# 3bp.net
KiCad netlist of a schematic drawn in EAGLE
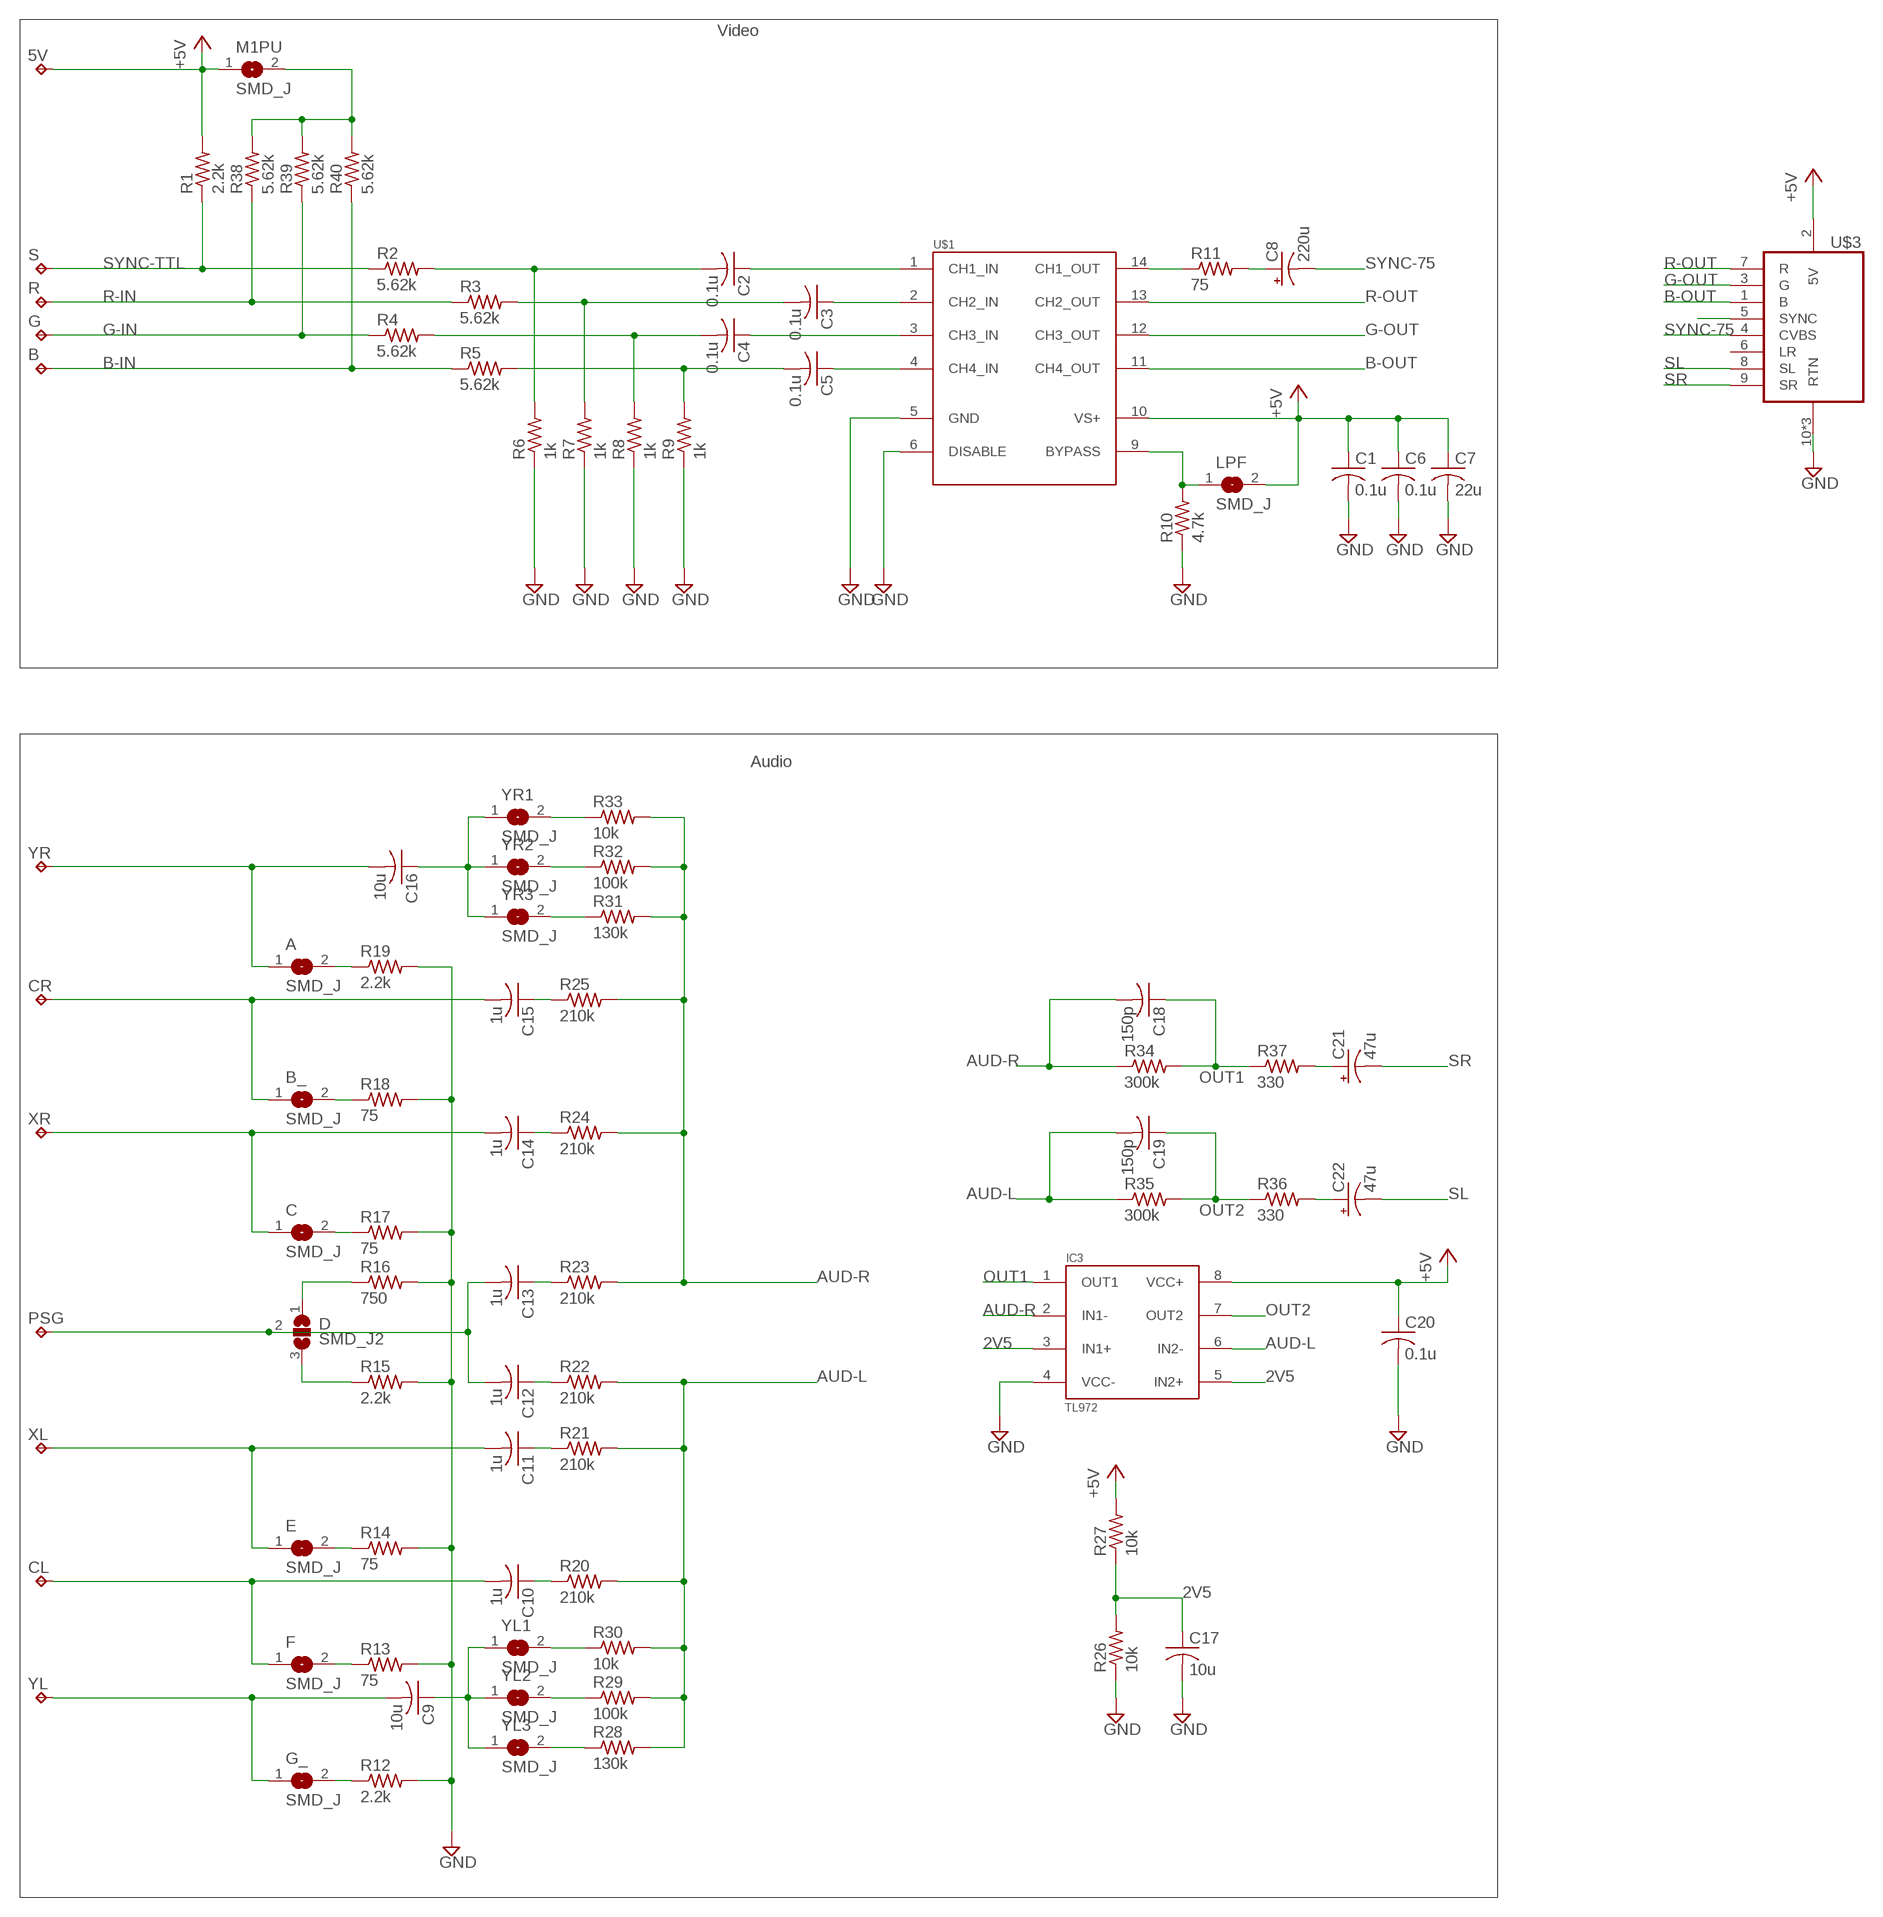
[diagram p0: schematic, sheet 1]

(export (version "E")
  (design (tool "Eeschema 10.0.6"))
  (components
    (comp (ref "5V")
      (value "PAD_50X80")
      (footprint "eagle-import:TP_50X80")
      (libsource (lib "eagle-import") (part "PAD_50X80"))
    )
    (comp (ref "A")
      (value "SMD_J")
      (footprint "eagle-import:SJ")
      (libsource (lib "eagle-import") (part "SMD_J"))
    )
    (comp (ref "B")
      (value "PAD_50X80")
      (footprint "eagle-import:TP_50X80")
      (libsource (lib "eagle-import") (part "PAD_50X80"))
    )
    (comp (ref "B_")
      (value "SMD_J")
      (footprint "eagle-import:SJ")
      (libsource (lib "eagle-import") (part "SMD_J"))
    )
    (comp (ref "C")
      (value "SMD_J")
      (footprint "eagle-import:SJ")
      (libsource (lib "eagle-import") (part "SMD_J"))
    )
    (comp (ref "C1")
      (value "0.1u")
      (footprint "eagle-import:C0603")
      (libsource (lib "eagle-import") (part "C-USC0603"))
    )
    (comp (ref "C2")
      (value "0.1u")
      (footprint "eagle-import:C0603")
      (libsource (lib "eagle-import") (part "C-USC0603"))
    )
    (comp (ref "C3")
      (value "0.1u")
      (footprint "eagle-import:C0603")
      (libsource (lib "eagle-import") (part "C-USC0603"))
    )
    (comp (ref "C4")
      (value "0.1u")
      (footprint "eagle-import:C0603")
      (libsource (lib "eagle-import") (part "C-USC0603"))
    )
    (comp (ref "C5")
      (value "0.1u")
      (footprint "eagle-import:C0603")
      (libsource (lib "eagle-import") (part "C-USC0603"))
    )
    (comp (ref "C6")
      (value "0.1u")
      (footprint "eagle-import:C0603")
      (libsource (lib "eagle-import") (part "C-USC0603"))
    )
    (comp (ref "C7")
      (value "22u")
      (footprint "eagle-import:C1206")
      (libsource (lib "eagle-import") (part "C-USC1206"))
    )
    (comp (ref "C8")
      (value "220u")
      (footprint "eagle-import:CT3528")
      (libsource (lib "eagle-import") (part "CPOL-USCT3528"))
    )
    (comp (ref "C9")
      (value "10u")
      (footprint "eagle-import:C0805")
      (libsource (lib "eagle-import") (part "C-USC0805"))
    )
    (comp (ref "C10")
      (value "1u")
      (footprint "eagle-import:C0603")
      (libsource (lib "eagle-import") (part "C-USC0603"))
    )
    (comp (ref "C11")
      (value "1u")
      (footprint "eagle-import:C0603")
      (libsource (lib "eagle-import") (part "C-USC0603"))
    )
    (comp (ref "C12")
      (value "1u")
      (footprint "eagle-import:C0603")
      (libsource (lib "eagle-import") (part "C-USC0603"))
    )
    (comp (ref "C13")
      (value "1u")
      (footprint "eagle-import:C0603")
      (libsource (lib "eagle-import") (part "C-USC0603"))
    )
    (comp (ref "C14")
      (value "1u")
      (footprint "eagle-import:C0603")
      (libsource (lib "eagle-import") (part "C-USC0603"))
    )
    (comp (ref "C15")
      (value "1u")
      (footprint "eagle-import:C0603")
      (libsource (lib "eagle-import") (part "C-USC0603"))
    )
    (comp (ref "C16")
      (value "10u")
      (footprint "eagle-import:C0805")
      (libsource (lib "eagle-import") (part "C-USC0805"))
    )
    (comp (ref "C17")
      (value "10u")
      (footprint "eagle-import:C1206")
      (libsource (lib "eagle-import") (part "C-USC1206"))
    )
    (comp (ref "C18")
      (value "150p")
      (footprint "eagle-import:C0603")
      (libsource (lib "eagle-import") (part "C-USC0603"))
    )
    (comp (ref "C19")
      (value "150p")
      (footprint "eagle-import:C0603")
      (libsource (lib "eagle-import") (part "C-USC0603"))
    )
    (comp (ref "C20")
      (value "0.1u")
      (footprint "eagle-import:C0603")
      (libsource (lib "eagle-import") (part "C-USC0603"))
    )
    (comp (ref "C21")
      (value "47u")
      (footprint "eagle-import:CT3528")
      (libsource (lib "eagle-import") (part "CPOL-USCT3528"))
    )
    (comp (ref "C22")
      (value "47u")
      (footprint "eagle-import:CT3528")
      (libsource (lib "eagle-import") (part "CPOL-USCT3528"))
    )
    (comp (ref "CL")
      (value "PAD_50X80")
      (footprint "eagle-import:TP_50X80")
      (libsource (lib "eagle-import") (part "PAD_50X80"))
    )
    (comp (ref "CR")
      (value "PAD_50X80")
      (footprint "eagle-import:TP_50X80")
      (libsource (lib "eagle-import") (part "PAD_50X80"))
    )
    (comp (ref "D")
      (value "SMD_J2")
      (footprint "eagle-import:SJ_2")
      (libsource (lib "eagle-import") (part "SMD_J2"))
    )
    (comp (ref "E")
      (value "SMD_J")
      (footprint "eagle-import:SJ")
      (libsource (lib "eagle-import") (part "SMD_J"))
    )
    (comp (ref "F")
      (value "SMD_J")
      (footprint "eagle-import:SJ")
      (libsource (lib "eagle-import") (part "SMD_J"))
    )
    (comp (ref "G")
      (value "PAD_50X80")
      (footprint "eagle-import:TP_50X80")
      (libsource (lib "eagle-import") (part "PAD_50X80"))
    )
    (comp (ref "G_")
      (value "SMD_J")
      (footprint "eagle-import:SJ")
      (libsource (lib "eagle-import") (part "SMD_J"))
    )
    (comp (ref "IC3")
      (value "TL972")
      (footprint "eagle-import:SOIC8")
      (libsource (lib "eagle-import") (part "TL972"))
    )
    (comp (ref "LPF")
      (value "SMD_J")
      (footprint "eagle-import:SJ")
      (libsource (lib "eagle-import") (part "SMD_J"))
    )
    (comp (ref "M1PU")
      (value "SMD_J")
      (footprint "eagle-import:SJ")
      (libsource (lib "eagle-import") (part "SMD_J"))
    )
    (comp (ref "PSG")
      (value "PAD_50X80")
      (footprint "eagle-import:TP_50X80")
      (libsource (lib "eagle-import") (part "PAD_50X80"))
    )
    (comp (ref "R")
      (value "PAD_50X80")
      (footprint "eagle-import:TP_50X80")
      (libsource (lib "eagle-import") (part "PAD_50X80"))
    )
    (comp (ref "R1")
      (value "2.2k")
      (footprint "eagle-import:R0603")
      (libsource (lib "eagle-import") (part "R-US_R0603"))
    )
    (comp (ref "R2")
      (value "5.62k")
      (footprint "eagle-import:R0603")
      (libsource (lib "eagle-import") (part "R-US_R0603"))
    )
    (comp (ref "R3")
      (value "5.62k")
      (footprint "eagle-import:R0603")
      (libsource (lib "eagle-import") (part "R-US_R0603"))
    )
    (comp (ref "R4")
      (value "5.62k")
      (footprint "eagle-import:R0603")
      (libsource (lib "eagle-import") (part "R-US_R0603"))
    )
    (comp (ref "R5")
      (value "5.62k")
      (footprint "eagle-import:R0603")
      (libsource (lib "eagle-import") (part "R-US_R0603"))
    )
    (comp (ref "R6")
      (value "1k")
      (footprint "eagle-import:R0603")
      (libsource (lib "eagle-import") (part "R-US_R0603"))
    )
    (comp (ref "R7")
      (value "1k")
      (footprint "eagle-import:R0603")
      (libsource (lib "eagle-import") (part "R-US_R0603"))
    )
    (comp (ref "R8")
      (value "1k")
      (footprint "eagle-import:R0603")
      (libsource (lib "eagle-import") (part "R-US_R0603"))
    )
    (comp (ref "R9")
      (value "1k")
      (footprint "eagle-import:R0603")
      (libsource (lib "eagle-import") (part "R-US_R0603"))
    )
    (comp (ref "R10")
      (value "4.7k")
      (footprint "eagle-import:R0603")
      (libsource (lib "eagle-import") (part "R-US_R0603"))
    )
    (comp (ref "R11")
      (value "75")
      (footprint "eagle-import:R0603")
      (libsource (lib "eagle-import") (part "R-US_R0603"))
    )
    (comp (ref "R12")
      (value "2.2k")
      (footprint "eagle-import:R0603")
      (libsource (lib "eagle-import") (part "R-US_R0603"))
    )
    (comp (ref "R13")
      (value "75")
      (footprint "eagle-import:R0603")
      (libsource (lib "eagle-import") (part "R-US_R0603"))
    )
    (comp (ref "R14")
      (value "75")
      (footprint "eagle-import:R0603")
      (libsource (lib "eagle-import") (part "R-US_R0603"))
    )
    (comp (ref "R15")
      (value "2.2k")
      (footprint "eagle-import:R0603")
      (libsource (lib "eagle-import") (part "R-US_R0603"))
    )
    (comp (ref "R16")
      (value "750")
      (footprint "eagle-import:R0603")
      (libsource (lib "eagle-import") (part "R-US_R0603"))
    )
    (comp (ref "R17")
      (value "75")
      (footprint "eagle-import:R0603")
      (libsource (lib "eagle-import") (part "R-US_R0603"))
    )
    (comp (ref "R18")
      (value "75")
      (footprint "eagle-import:R0603")
      (libsource (lib "eagle-import") (part "R-US_R0603"))
    )
    (comp (ref "R19")
      (value "2.2k")
      (footprint "eagle-import:R0603")
      (libsource (lib "eagle-import") (part "R-US_R0603"))
    )
    (comp (ref "R20")
      (value "210k")
      (footprint "eagle-import:R0603")
      (libsource (lib "eagle-import") (part "R-US_R0603"))
    )
    (comp (ref "R21")
      (value "210k")
      (footprint "eagle-import:R0603")
      (libsource (lib "eagle-import") (part "R-US_R0603"))
    )
    (comp (ref "R22")
      (value "210k")
      (footprint "eagle-import:R0603")
      (libsource (lib "eagle-import") (part "R-US_R0603"))
    )
    (comp (ref "R23")
      (value "210k")
      (footprint "eagle-import:R0603")
      (libsource (lib "eagle-import") (part "R-US_R0603"))
    )
    (comp (ref "R24")
      (value "210k")
      (footprint "eagle-import:R0603")
      (libsource (lib "eagle-import") (part "R-US_R0603"))
    )
    (comp (ref "R25")
      (value "210k")
      (footprint "eagle-import:R0603")
      (libsource (lib "eagle-import") (part "R-US_R0603"))
    )
    (comp (ref "R26")
      (value "10k")
      (footprint "eagle-import:R0603")
      (libsource (lib "eagle-import") (part "R-US_R0603"))
    )
    (comp (ref "R27")
      (value "10k")
      (footprint "eagle-import:R0603")
      (libsource (lib "eagle-import") (part "R-US_R0603"))
    )
    (comp (ref "R28")
      (value "130k")
      (footprint "eagle-import:R0603")
      (libsource (lib "eagle-import") (part "R-US_R0603"))
    )
    (comp (ref "R29")
      (value "100k")
      (footprint "eagle-import:R0603")
      (libsource (lib "eagle-import") (part "R-US_R0603"))
    )
    (comp (ref "R30")
      (value "10k")
      (footprint "eagle-import:R0603")
      (libsource (lib "eagle-import") (part "R-US_R0603"))
    )
    (comp (ref "R31")
      (value "130k")
      (footprint "eagle-import:R0603")
      (libsource (lib "eagle-import") (part "R-US_R0603"))
    )
    (comp (ref "R32")
      (value "100k")
      (footprint "eagle-import:R0603")
      (libsource (lib "eagle-import") (part "R-US_R0603"))
    )
    (comp (ref "R33")
      (value "10k")
      (footprint "eagle-import:R0603")
      (libsource (lib "eagle-import") (part "R-US_R0603"))
    )
    (comp (ref "R34")
      (value "300k")
      (footprint "eagle-import:R0603")
      (libsource (lib "eagle-import") (part "R-US_R0603"))
    )
    (comp (ref "R35")
      (value "300k")
      (footprint "eagle-import:R0603")
      (libsource (lib "eagle-import") (part "R-US_R0603"))
    )
    (comp (ref "R36")
      (value "330")
      (footprint "eagle-import:R0603")
      (libsource (lib "eagle-import") (part "R-US_R0603"))
    )
    (comp (ref "R37")
      (value "330")
      (footprint "eagle-import:R0603")
      (libsource (lib "eagle-import") (part "R-US_R0603"))
    )
    (comp (ref "R38")
      (value "5.62k")
      (footprint "eagle-import:R0603")
      (libsource (lib "eagle-import") (part "R-US_R0603"))
    )
    (comp (ref "R39")
      (value "5.62k")
      (footprint "eagle-import:R0603")
      (libsource (lib "eagle-import") (part "R-US_R0603"))
    )
    (comp (ref "R40")
      (value "5.62k")
      (footprint "eagle-import:R0603")
      (libsource (lib "eagle-import") (part "R-US_R0603"))
    )
    (comp (ref "S")
      (value "PAD_50X80")
      (footprint "eagle-import:TP_50X80")
      (libsource (lib "eagle-import") (part "PAD_50X80"))
    )
    (comp (ref "U$1")
      (value "THS7374IPWR")
      (footprint "eagle-import:TSSOP14")
      (libsource (lib "eagle-import") (part "THS7374IPWR"))
    )
    (comp (ref "U$3")
      (value "MD-90SM")
      (footprint "eagle-import:MD90SM")
      (libsource (lib "eagle-import") (part "MD-90SM"))
    )
    (comp (ref "XL")
      (value "PAD_50X80")
      (footprint "eagle-import:TP_50X80")
      (libsource (lib "eagle-import") (part "PAD_50X80"))
    )
    (comp (ref "XR")
      (value "PAD_50X80")
      (footprint "eagle-import:TP_50X80")
      (libsource (lib "eagle-import") (part "PAD_50X80"))
    )
    (comp (ref "YL")
      (value "PAD_50X80")
      (footprint "eagle-import:TP_50X80")
      (libsource (lib "eagle-import") (part "PAD_50X80"))
    )
    (comp (ref "YL1")
      (value "SMD_J")
      (footprint "eagle-import:SJ")
      (libsource (lib "eagle-import") (part "SMD_J"))
    )
    (comp (ref "YL2")
      (value "SMD_J")
      (footprint "eagle-import:SJ")
      (libsource (lib "eagle-import") (part "SMD_J"))
    )
    (comp (ref "YL3")
      (value "SMD_J")
      (footprint "eagle-import:SJ")
      (libsource (lib "eagle-import") (part "SMD_J"))
    )
    (comp (ref "YR")
      (value "PAD_50X80")
      (footprint "eagle-import:TP_50X80")
      (libsource (lib "eagle-import") (part "PAD_50X80"))
    )
    (comp (ref "YR1")
      (value "SMD_J")
      (footprint "eagle-import:SJ")
      (libsource (lib "eagle-import") (part "SMD_J"))
    )
    (comp (ref "YR2")
      (value "SMD_J")
      (footprint "eagle-import:SJ")
      (libsource (lib "eagle-import") (part "SMD_J"))
    )
    (comp (ref "YR3")
      (value "SMD_J")
      (footprint "eagle-import:SJ")
      (libsource (lib "eagle-import") (part "SMD_J"))
    )
  )
  (nets
    (net (code "1") (name "+5V") (class "Default")
      (node (ref "5V") (pin "TP") (pinfunction "TP_TP") (pintype "input"))
      (node (ref "C1") (pin "1") (pinfunction "1_1") (pintype "passive"))
      (node (ref "C20") (pin "1") (pinfunction "1_1") (pintype "passive"))
      (node (ref "C6") (pin "1") (pinfunction "1_1") (pintype "passive"))
      (node (ref "C7") (pin "1") (pinfunction "1_1") (pintype "passive"))
      (node (ref "IC3") (pin "8") (pinfunction "VCC+_8") (pintype "bidirectional"))
      (node (ref "LPF") (pin "2") (pinfunction "2_2") (pintype "passive"))
      (node (ref "M1PU") (pin "1") (pinfunction "1_1") (pintype "passive"))
      (node (ref "R1") (pin "2") (pinfunction "2_2") (pintype "passive"))
      (node (ref "R27") (pin "2") (pinfunction "2_2") (pintype "passive"))
      (node (ref "U$1") (pin "10") (pinfunction "VS+_10") (pintype "bidirectional"))
      (node (ref "U$3") (pin "2") (pinfunction "5V_2") (pintype "bidirectional"))
    )
    (net (code "2") (name "/2V5") (class "Default")
      (node (ref "C17") (pin "1") (pinfunction "1_1") (pintype "passive"))
      (node (ref "IC3") (pin "3") (pinfunction "IN1+_3") (pintype "bidirectional"))
      (node (ref "IC3") (pin "5") (pinfunction "IN2+_5") (pintype "bidirectional"))
      (node (ref "R26") (pin "2") (pinfunction "2_2") (pintype "passive"))
      (node (ref "R27") (pin "1") (pinfunction "1_1") (pintype "passive"))
    )
    (net (code "3") (name "/AUD-L") (class "Default")
      (node (ref "C19") (pin "2") (pinfunction "2_2") (pintype "passive"))
      (node (ref "IC3") (pin "6") (pinfunction "IN2-_6") (pintype "bidirectional"))
      (node (ref "R20") (pin "2") (pinfunction "2_2") (pintype "passive"))
      (node (ref "R21") (pin "2") (pinfunction "2_2") (pintype "passive"))
      (node (ref "R22") (pin "2") (pinfunction "2_2") (pintype "passive"))
      (node (ref "R28") (pin "2") (pinfunction "2_2") (pintype "passive"))
      (node (ref "R29") (pin "2") (pinfunction "2_2") (pintype "passive"))
      (node (ref "R30") (pin "2") (pinfunction "2_2") (pintype "passive"))
      (node (ref "R35") (pin "1") (pinfunction "1_1") (pintype "passive"))
    )
    (net (code "4") (name "/AUD-R") (class "Default")
      (node (ref "C18") (pin "2") (pinfunction "2_2") (pintype "passive"))
      (node (ref "IC3") (pin "2") (pinfunction "IN1-_2") (pintype "bidirectional"))
      (node (ref "R23") (pin "2") (pinfunction "2_2") (pintype "passive"))
      (node (ref "R24") (pin "2") (pinfunction "2_2") (pintype "passive"))
      (node (ref "R25") (pin "2") (pinfunction "2_2") (pintype "passive"))
      (node (ref "R31") (pin "2") (pinfunction "2_2") (pintype "passive"))
      (node (ref "R32") (pin "2") (pinfunction "2_2") (pintype "passive"))
      (node (ref "R33") (pin "2") (pinfunction "2_2") (pintype "passive"))
      (node (ref "R34") (pin "1") (pinfunction "1_1") (pintype "passive"))
    )
    (net (code "5") (name "/B-IN") (class "Default")
      (node (ref "B") (pin "TP") (pinfunction "TP_TP") (pintype "input"))
      (node (ref "R40") (pin "1") (pinfunction "1_1") (pintype "passive"))
      (node (ref "R5") (pin "1") (pinfunction "1_1") (pintype "passive"))
    )
    (net (code "6") (name "/B-OUT") (class "Default")
      (node (ref "U$1") (pin "11") (pinfunction "CH4_OUT_11") (pintype "bidirectional"))
      (node (ref "U$3") (pin "1") (pinfunction "B_1") (pintype "bidirectional"))
    )
    (net (code "7") (name "/G-IN") (class "Default")
      (node (ref "G") (pin "TP") (pinfunction "TP_TP") (pintype "input"))
      (node (ref "R39") (pin "1") (pinfunction "1_1") (pintype "passive"))
      (node (ref "R4") (pin "1") (pinfunction "1_1") (pintype "passive"))
    )
    (net (code "8") (name "/G-OUT") (class "Default")
      (node (ref "U$1") (pin "12") (pinfunction "CH3_OUT_12") (pintype "bidirectional"))
      (node (ref "U$3") (pin "3") (pinfunction "G_3") (pintype "bidirectional"))
    )
    (net (code "9") (name "/OUT1") (class "Default")
      (node (ref "C18") (pin "1") (pinfunction "1_1") (pintype "passive"))
      (node (ref "IC3") (pin "1") (pinfunction "OUT1_1") (pintype "bidirectional"))
      (node (ref "R34") (pin "2") (pinfunction "2_2") (pintype "passive"))
      (node (ref "R37") (pin "1") (pinfunction "1_1") (pintype "passive"))
    )
    (net (code "10") (name "/OUT2") (class "Default")
      (node (ref "C19") (pin "1") (pinfunction "1_1") (pintype "passive"))
      (node (ref "IC3") (pin "7") (pinfunction "OUT2_7") (pintype "bidirectional"))
      (node (ref "R35") (pin "2") (pinfunction "2_2") (pintype "passive"))
      (node (ref "R36") (pin "1") (pinfunction "1_1") (pintype "passive"))
    )
    (net (code "11") (name "/R-IN") (class "Default")
      (node (ref "R") (pin "TP") (pinfunction "TP_TP") (pintype "input"))
      (node (ref "R3") (pin "1") (pinfunction "1_1") (pintype "passive"))
      (node (ref "R38") (pin "1") (pinfunction "1_1") (pintype "passive"))
    )
    (net (code "12") (name "/R-OUT") (class "Default")
      (node (ref "U$1") (pin "13") (pinfunction "CH2_OUT_13") (pintype "bidirectional"))
      (node (ref "U$3") (pin "7") (pinfunction "R_7") (pintype "bidirectional"))
    )
    (net (code "13") (name "/SL") (class "Default")
      (node (ref "C22") (pin "-") (pinfunction "-_-") (pintype "passive"))
      (node (ref "U$3") (pin "8") (pinfunction "SL_8") (pintype "bidirectional"))
    )
    (net (code "14") (name "/SR") (class "Default")
      (node (ref "C21") (pin "-") (pinfunction "-_-") (pintype "passive"))
      (node (ref "U$3") (pin "9") (pinfunction "SR_9") (pintype "bidirectional"))
    )
    (net (code "15") (name "/SYNC-75") (class "Default")
      (node (ref "C8") (pin "-") (pinfunction "-_-") (pintype "passive"))
      (node (ref "U$3") (pin "4") (pinfunction "CVBS_4") (pintype "bidirectional"))
    )
    (net (code "16") (name "/SYNC-TTL") (class "Default")
      (node (ref "R1") (pin "1") (pinfunction "1_1") (pintype "passive"))
      (node (ref "R2") (pin "1") (pinfunction "1_1") (pintype "passive"))
      (node (ref "S") (pin "TP") (pinfunction "TP_TP") (pintype "input"))
    )
    (net (code "17") (name "GND") (class "Default")
      (node (ref "C1") (pin "2") (pinfunction "2_2") (pintype "passive"))
      (node (ref "C17") (pin "2") (pinfunction "2_2") (pintype "passive"))
      (node (ref "C20") (pin "2") (pinfunction "2_2") (pintype "passive"))
      (node (ref "C6") (pin "2") (pinfunction "2_2") (pintype "passive"))
      (node (ref "C7") (pin "2") (pinfunction "2_2") (pintype "passive"))
      (node (ref "IC3") (pin "4") (pinfunction "VCC-_4") (pintype "bidirectional"))
      (node (ref "R10") (pin "1") (pinfunction "1_1") (pintype "passive"))
      (node (ref "R12") (pin "2") (pinfunction "2_2") (pintype "passive"))
      (node (ref "R13") (pin "2") (pinfunction "2_2") (pintype "passive"))
      (node (ref "R14") (pin "2") (pinfunction "2_2") (pintype "passive"))
      (node (ref "R15") (pin "2") (pinfunction "2_2") (pintype "passive"))
      (node (ref "R16") (pin "2") (pinfunction "2_2") (pintype "passive"))
      (node (ref "R17") (pin "2") (pinfunction "2_2") (pintype "passive"))
      (node (ref "R18") (pin "2") (pinfunction "2_2") (pintype "passive"))
      (node (ref "R19") (pin "2") (pinfunction "2_2") (pintype "passive"))
      (node (ref "R26") (pin "1") (pinfunction "1_1") (pintype "passive"))
      (node (ref "R6") (pin "1") (pinfunction "1_1") (pintype "passive"))
      (node (ref "R7") (pin "1") (pinfunction "1_1") (pintype "passive"))
      (node (ref "R8") (pin "1") (pinfunction "1_1") (pintype "passive"))
      (node (ref "R9") (pin "1") (pinfunction "1_1") (pintype "passive"))
      (node (ref "U$1") (pin "5") (pinfunction "GND_5") (pintype "bidirectional"))
      (node (ref "U$1") (pin "6") (pinfunction "DISABLE_6") (pintype "bidirectional"))
      (node (ref "U$3") (pin "10") (pinfunction "RTN_10") (pintype "bidirectional"))
      (node (ref "U$3") (pin "11") (pinfunction "RTN_11") (pintype "bidirectional"))
      (node (ref "U$3") (pin "12") (pinfunction "RTN_12") (pintype "bidirectional"))
    )
    (net (code "18") (name "Net-(A-Pad1)") (class "Default")
      (node (ref "A") (pin "1") (pinfunction "1_1") (pintype "passive"))
      (node (ref "C16") (pin "2") (pinfunction "2_2") (pintype "passive"))
      (node (ref "YR") (pin "TP") (pinfunction "TP_TP") (pintype "input"))
    )
    (net (code "19") (name "Net-(A-Pad2)") (class "Default")
      (node (ref "A") (pin "2") (pinfunction "2_2") (pintype "passive"))
      (node (ref "R19") (pin "1") (pinfunction "1_1") (pintype "passive"))
    )
    (net (code "20") (name "Net-(B_-Pad1)") (class "Default")
      (node (ref "B_") (pin "1") (pinfunction "1_1") (pintype "passive"))
      (node (ref "C15") (pin "2") (pinfunction "2_2") (pintype "passive"))
      (node (ref "CR") (pin "TP") (pinfunction "TP_TP") (pintype "input"))
    )
    (net (code "21") (name "Net-(B_-Pad2)") (class "Default")
      (node (ref "B_") (pin "2") (pinfunction "2_2") (pintype "passive"))
      (node (ref "R18") (pin "1") (pinfunction "1_1") (pintype "passive"))
    )
    (net (code "22") (name "Net-(C-Pad1)") (class "Default")
      (node (ref "C") (pin "1") (pinfunction "1_1") (pintype "passive"))
      (node (ref "C14") (pin "2") (pinfunction "2_2") (pintype "passive"))
      (node (ref "XR") (pin "TP") (pinfunction "TP_TP") (pintype "input"))
    )
    (net (code "23") (name "Net-(C-Pad2)") (class "Default")
      (node (ref "C") (pin "2") (pinfunction "2_2") (pintype "passive"))
      (node (ref "R17") (pin "1") (pinfunction "1_1") (pintype "passive"))
    )
    (net (code "24") (name "Net-(C2-Pad2)") (class "Default")
      (node (ref "C2") (pin "2") (pinfunction "2_2") (pintype "passive"))
      (node (ref "R2") (pin "2") (pinfunction "2_2") (pintype "passive"))
      (node (ref "R6") (pin "2") (pinfunction "2_2") (pintype "passive"))
    )
    (net (code "25") (name "Net-(C3-Pad2)") (class "Default")
      (node (ref "C3") (pin "2") (pinfunction "2_2") (pintype "passive"))
      (node (ref "R3") (pin "2") (pinfunction "2_2") (pintype "passive"))
      (node (ref "R7") (pin "2") (pinfunction "2_2") (pintype "passive"))
    )
    (net (code "26") (name "Net-(C4-Pad2)") (class "Default")
      (node (ref "C4") (pin "2") (pinfunction "2_2") (pintype "passive"))
      (node (ref "R4") (pin "2") (pinfunction "2_2") (pintype "passive"))
      (node (ref "R8") (pin "2") (pinfunction "2_2") (pintype "passive"))
    )
    (net (code "27") (name "Net-(C5-Pad2)") (class "Default")
      (node (ref "C5") (pin "2") (pinfunction "2_2") (pintype "passive"))
      (node (ref "R5") (pin "2") (pinfunction "2_2") (pintype "passive"))
      (node (ref "R9") (pin "2") (pinfunction "2_2") (pintype "passive"))
    )
    (net (code "28") (name "Net-(C8-Pad+)") (class "Default")
      (node (ref "C8") (pin "+") (pinfunction "+_+") (pintype "passive"))
      (node (ref "R11") (pin "2") (pinfunction "2_2") (pintype "passive"))
    )
    (net (code "29") (name "Net-(C9-Pad1)") (class "Default")
      (node (ref "C9") (pin "1") (pinfunction "1_1") (pintype "passive"))
      (node (ref "YL1") (pin "1") (pinfunction "1_1") (pintype "passive"))
      (node (ref "YL2") (pin "1") (pinfunction "1_1") (pintype "passive"))
      (node (ref "YL3") (pin "1") (pinfunction "1_1") (pintype "passive"))
    )
    (net (code "30") (name "Net-(C9-Pad2)") (class "Default")
      (node (ref "C9") (pin "2") (pinfunction "2_2") (pintype "passive"))
      (node (ref "G_") (pin "1") (pinfunction "1_1") (pintype "passive"))
      (node (ref "YL") (pin "TP") (pinfunction "TP_TP") (pintype "input"))
    )
    (net (code "31") (name "Net-(C10-Pad1)") (class "Default")
      (node (ref "C10") (pin "1") (pinfunction "1_1") (pintype "passive"))
      (node (ref "R20") (pin "1") (pinfunction "1_1") (pintype "passive"))
    )
    (net (code "32") (name "Net-(C10-Pad2)") (class "Default")
      (node (ref "C10") (pin "2") (pinfunction "2_2") (pintype "passive"))
      (node (ref "CL") (pin "TP") (pinfunction "TP_TP") (pintype "input"))
      (node (ref "F") (pin "1") (pinfunction "1_1") (pintype "passive"))
    )
    (net (code "33") (name "Net-(C11-Pad1)") (class "Default")
      (node (ref "C11") (pin "1") (pinfunction "1_1") (pintype "passive"))
      (node (ref "R21") (pin "1") (pinfunction "1_1") (pintype "passive"))
    )
    (net (code "34") (name "Net-(C11-Pad2)") (class "Default")
      (node (ref "C11") (pin "2") (pinfunction "2_2") (pintype "passive"))
      (node (ref "E") (pin "1") (pinfunction "1_1") (pintype "passive"))
      (node (ref "XL") (pin "TP") (pinfunction "TP_TP") (pintype "input"))
    )
    (net (code "35") (name "Net-(C12-Pad1)") (class "Default")
      (node (ref "C12") (pin "1") (pinfunction "1_1") (pintype "passive"))
      (node (ref "R22") (pin "1") (pinfunction "1_1") (pintype "passive"))
    )
    (net (code "36") (name "Net-(C12-Pad2)") (class "Default")
      (node (ref "C12") (pin "2") (pinfunction "2_2") (pintype "passive"))
      (node (ref "C13") (pin "2") (pinfunction "2_2") (pintype "passive"))
      (node (ref "D") (pin "2") (pinfunction "2_2") (pintype "passive"))
      (node (ref "PSG") (pin "TP") (pinfunction "TP_TP") (pintype "input"))
    )
    (net (code "37") (name "Net-(C13-Pad1)") (class "Default")
      (node (ref "C13") (pin "1") (pinfunction "1_1") (pintype "passive"))
      (node (ref "R23") (pin "1") (pinfunction "1_1") (pintype "passive"))
    )
    (net (code "38") (name "Net-(C14-Pad1)") (class "Default")
      (node (ref "C14") (pin "1") (pinfunction "1_1") (pintype "passive"))
      (node (ref "R24") (pin "1") (pinfunction "1_1") (pintype "passive"))
    )
    (net (code "39") (name "Net-(C15-Pad1)") (class "Default")
      (node (ref "C15") (pin "1") (pinfunction "1_1") (pintype "passive"))
      (node (ref "R25") (pin "1") (pinfunction "1_1") (pintype "passive"))
    )
    (net (code "40") (name "Net-(C16-Pad1)") (class "Default")
      (node (ref "C16") (pin "1") (pinfunction "1_1") (pintype "passive"))
      (node (ref "YR1") (pin "1") (pinfunction "1_1") (pintype "passive"))
      (node (ref "YR2") (pin "1") (pinfunction "1_1") (pintype "passive"))
      (node (ref "YR3") (pin "1") (pinfunction "1_1") (pintype "passive"))
    )
    (net (code "41") (name "Net-(C21-Pad+)") (class "Default")
      (node (ref "C21") (pin "+") (pinfunction "+_+") (pintype "passive"))
      (node (ref "R37") (pin "2") (pinfunction "2_2") (pintype "passive"))
    )
    (net (code "42") (name "Net-(C22-Pad+)") (class "Default")
      (node (ref "C22") (pin "+") (pinfunction "+_+") (pintype "passive"))
      (node (ref "R36") (pin "2") (pinfunction "2_2") (pintype "passive"))
    )
    (net (code "43") (name "Net-(D-Pad1)") (class "Default")
      (node (ref "D") (pin "1") (pinfunction "1_1") (pintype "passive"))
      (node (ref "R16") (pin "1") (pinfunction "1_1") (pintype "passive"))
    )
    (net (code "44") (name "Net-(D-Pad3)") (class "Default")
      (node (ref "D") (pin "3") (pinfunction "3_3") (pintype "passive"))
      (node (ref "R15") (pin "1") (pinfunction "1_1") (pintype "passive"))
    )
    (net (code "45") (name "Net-(E-Pad2)") (class "Default")
      (node (ref "E") (pin "2") (pinfunction "2_2") (pintype "passive"))
      (node (ref "R14") (pin "1") (pinfunction "1_1") (pintype "passive"))
    )
    (net (code "46") (name "Net-(F-Pad2)") (class "Default")
      (node (ref "F") (pin "2") (pinfunction "2_2") (pintype "passive"))
      (node (ref "R13") (pin "1") (pinfunction "1_1") (pintype "passive"))
    )
    (net (code "47") (name "Net-(G_-Pad2)") (class "Default")
      (node (ref "G_") (pin "2") (pinfunction "2_2") (pintype "passive"))
      (node (ref "R12") (pin "1") (pinfunction "1_1") (pintype "passive"))
    )
    (net (code "48") (name "Net-(M1PU-Pad2)") (class "Default")
      (node (ref "M1PU") (pin "2") (pinfunction "2_2") (pintype "passive"))
      (node (ref "R38") (pin "2") (pinfunction "2_2") (pintype "passive"))
      (node (ref "R39") (pin "2") (pinfunction "2_2") (pintype "passive"))
      (node (ref "R40") (pin "2") (pinfunction "2_2") (pintype "passive"))
    )
    (net (code "49") (name "Net-(R28-Pad1)") (class "Default")
      (node (ref "R28") (pin "1") (pinfunction "1_1") (pintype "passive"))
      (node (ref "YL3") (pin "2") (pinfunction "2_2") (pintype "passive"))
    )
    (net (code "50") (name "Net-(R29-Pad1)") (class "Default")
      (node (ref "R29") (pin "1") (pinfunction "1_1") (pintype "passive"))
      (node (ref "YL2") (pin "2") (pinfunction "2_2") (pintype "passive"))
    )
    (net (code "51") (name "Net-(R30-Pad1)") (class "Default")
      (node (ref "R30") (pin "1") (pinfunction "1_1") (pintype "passive"))
      (node (ref "YL1") (pin "2") (pinfunction "2_2") (pintype "passive"))
    )
    (net (code "52") (name "Net-(R31-Pad1)") (class "Default")
      (node (ref "R31") (pin "1") (pinfunction "1_1") (pintype "passive"))
      (node (ref "YR3") (pin "2") (pinfunction "2_2") (pintype "passive"))
    )
    (net (code "53") (name "Net-(R32-Pad1)") (class "Default")
      (node (ref "R32") (pin "1") (pinfunction "1_1") (pintype "passive"))
      (node (ref "YR2") (pin "2") (pinfunction "2_2") (pintype "passive"))
    )
    (net (code "54") (name "Net-(R33-Pad1)") (class "Default")
      (node (ref "R33") (pin "1") (pinfunction "1_1") (pintype "passive"))
      (node (ref "YR1") (pin "2") (pinfunction "2_2") (pintype "passive"))
    )
    (net (code "55") (name "Net-(U$1-BYPASS)") (class "Default")
      (node (ref "LPF") (pin "1") (pinfunction "1_1") (pintype "passive"))
      (node (ref "R10") (pin "2") (pinfunction "2_2") (pintype "passive"))
      (node (ref "U$1") (pin "9") (pinfunction "BYPASS_9") (pintype "bidirectional"))
    )
    (net (code "56") (name "Net-(U$1-CH1_IN)") (class "Default")
      (node (ref "C2") (pin "1") (pinfunction "1_1") (pintype "passive"))
      (node (ref "U$1") (pin "1") (pinfunction "CH1_IN_1") (pintype "bidirectional"))
    )
    (net (code "57") (name "Net-(U$1-CH1_OUT)") (class "Default")
      (node (ref "R11") (pin "1") (pinfunction "1_1") (pintype "passive"))
      (node (ref "U$1") (pin "14") (pinfunction "CH1_OUT_14") (pintype "bidirectional"))
    )
    (net (code "58") (name "Net-(U$1-CH2_IN)") (class "Default")
      (node (ref "C3") (pin "1") (pinfunction "1_1") (pintype "passive"))
      (node (ref "U$1") (pin "2") (pinfunction "CH2_IN_2") (pintype "bidirectional"))
    )
    (net (code "59") (name "Net-(U$1-CH3_IN)") (class "Default")
      (node (ref "C4") (pin "1") (pinfunction "1_1") (pintype "passive"))
      (node (ref "U$1") (pin "3") (pinfunction "CH3_IN_3") (pintype "bidirectional"))
    )
    (net (code "60") (name "Net-(U$1-CH4_IN)") (class "Default")
      (node (ref "C5") (pin "1") (pinfunction "1_1") (pintype "passive"))
      (node (ref "U$1") (pin "4") (pinfunction "CH4_IN_4") (pintype "bidirectional"))
    )
    (net (code "61") (name "unconnected-(U$3-LR-Pad6)") (class "Default")
      (node (ref "U$3") (pin "6") (pinfunction "LR_6") (pintype "bidirectional"))
    )
    (net (code "62") (name "unconnected-(U$3-SYNC-Pad5)") (class "Default")
      (node (ref "U$3") (pin "5") (pinfunction "SYNC_5") (pintype "bidirectional"))
    )
  )
)
